# cameraboardschematic.net
KiCad netlist of a schematic drawn in EasyEDA Pro
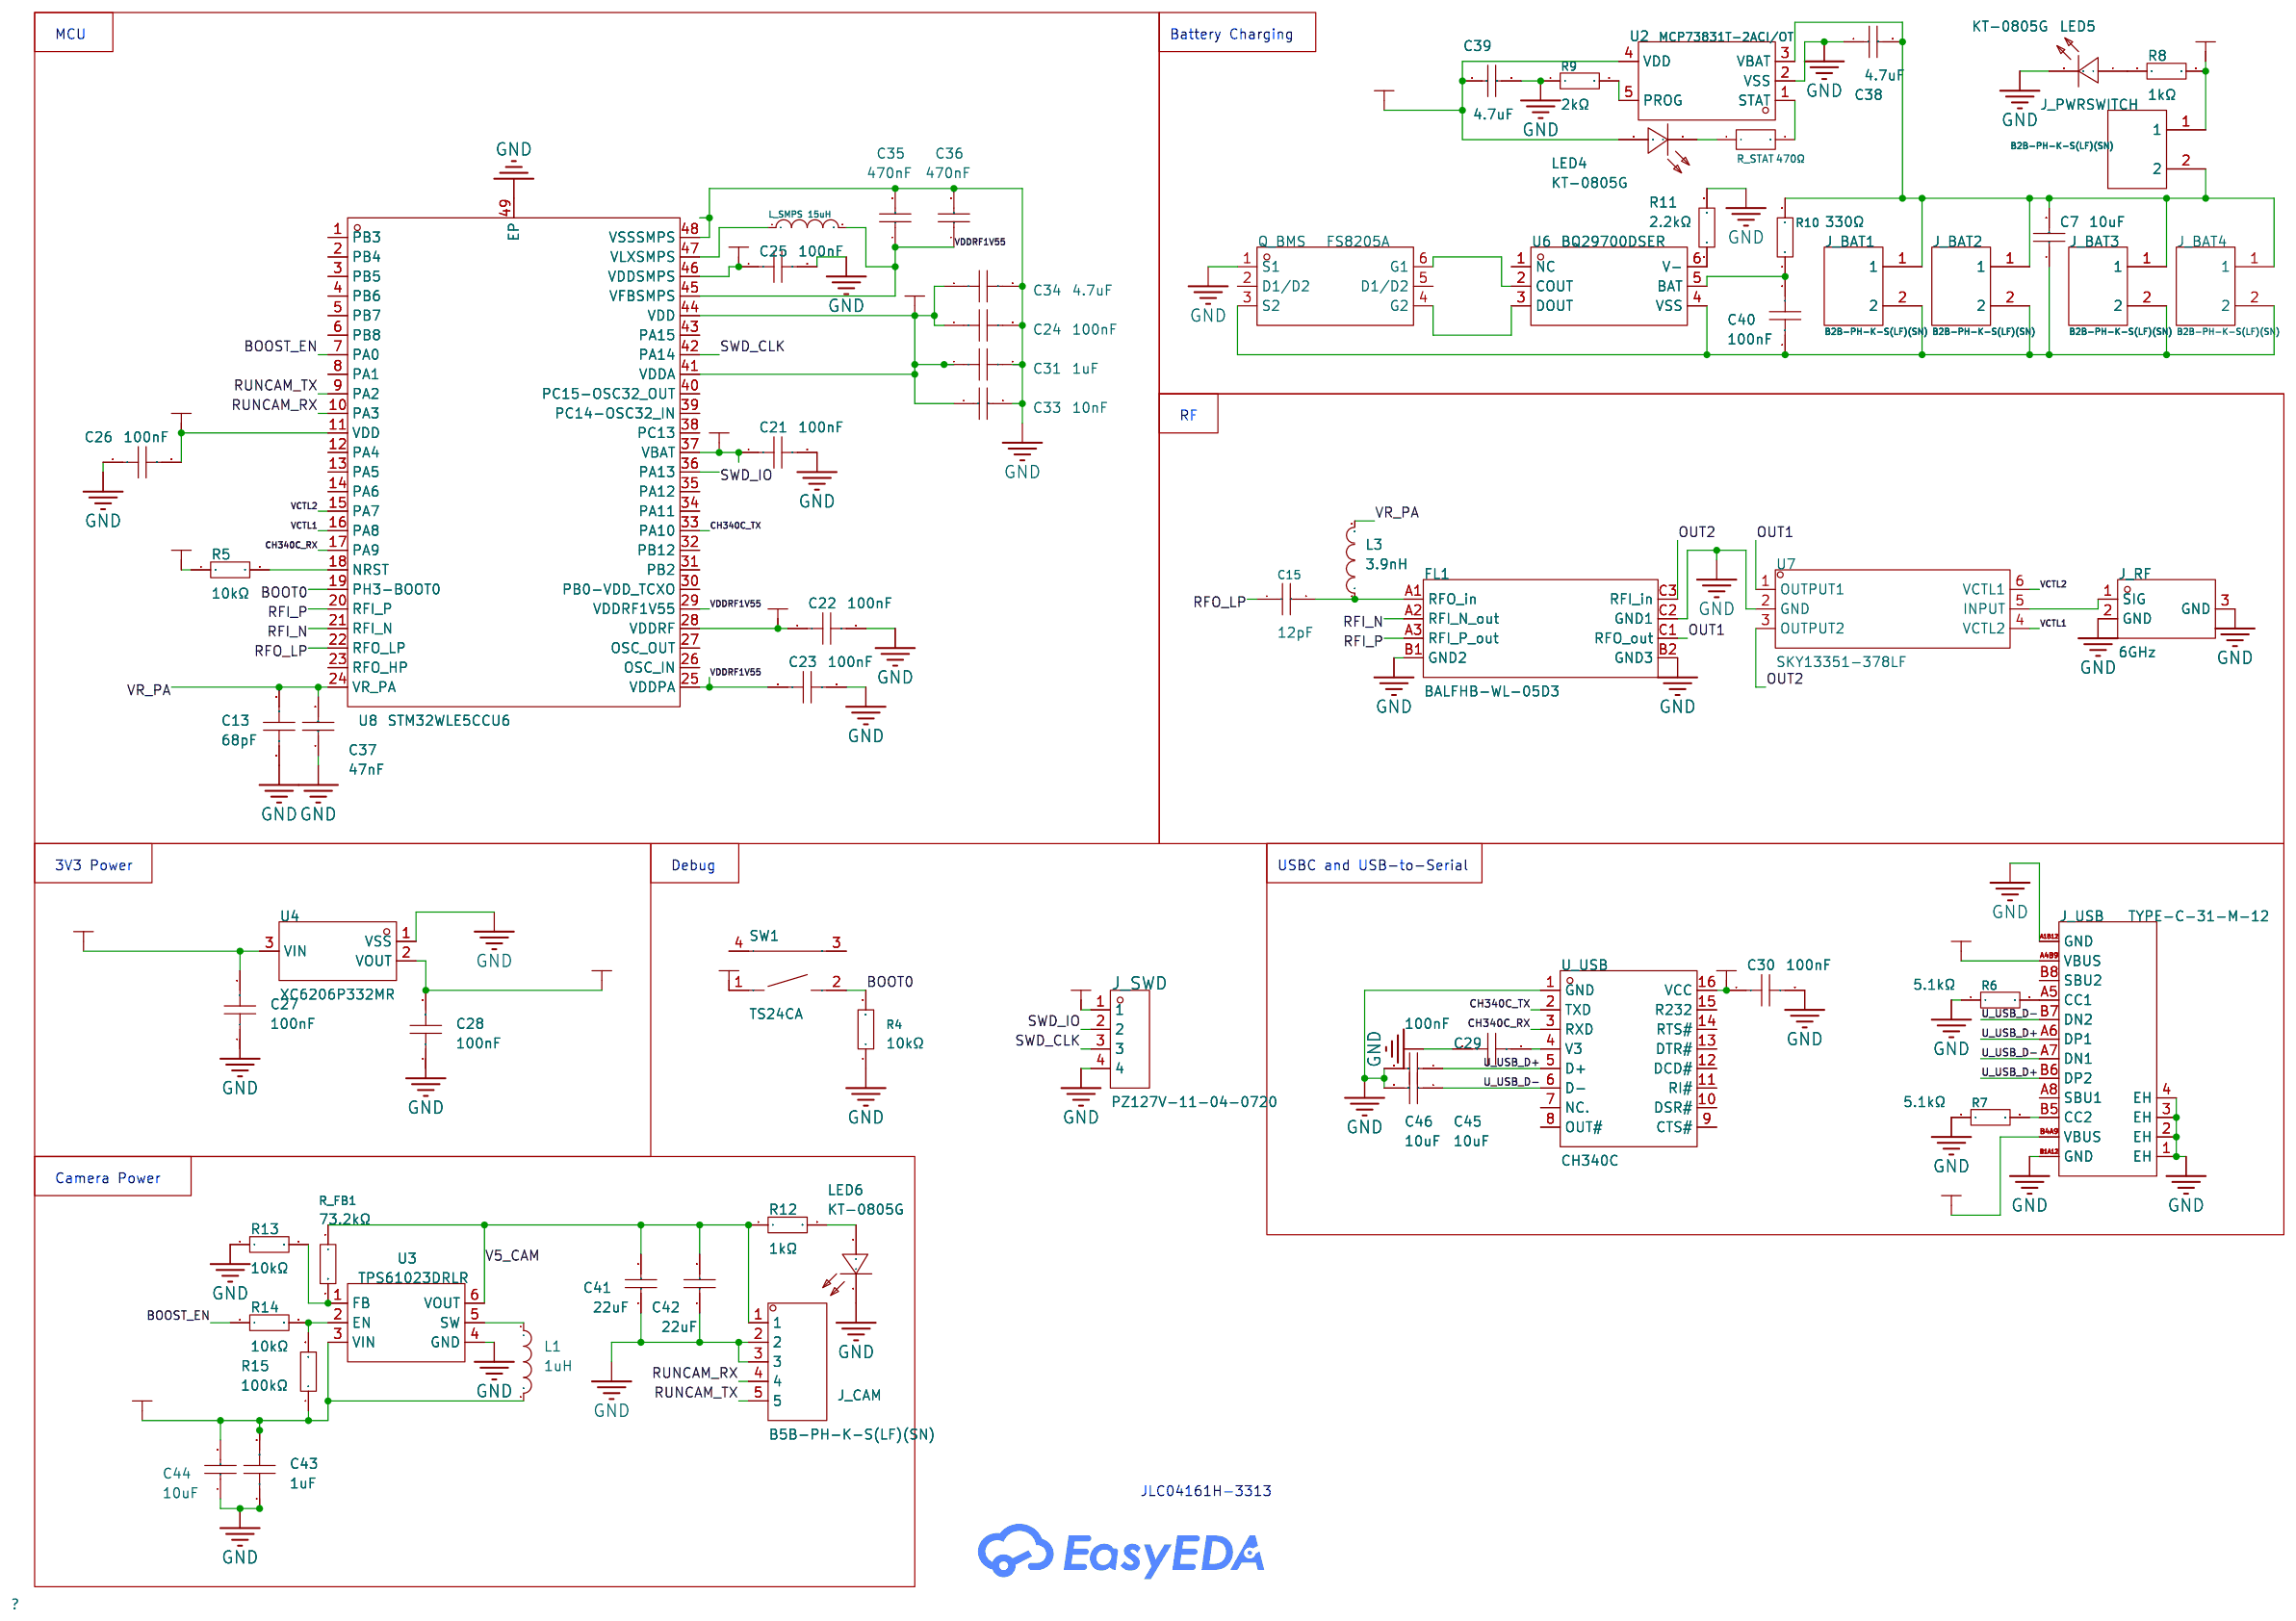
[diagram p0: schematic sheet]

(export (version "E")
  (design (tool "Eeschema 10.0.6"))
  (components
    (comp (ref "C7")
      (value "10uF")
      (footprint "easyedapro:C0402")
      (description "Capacitance:10uF Tolerance:±20% Tolerance:±20% Voltage Rating:6.3V Temperature Coefficient:X5R")
      (fields
        (field (name "Manufacturer Part") "CL05A106MQ5NUNC")
        (field (name "Manufacturer") "SAMSUNG(三星)")
      )
      (libsource (lib "easyedapro") (part "CL05A106MQ5NUNC"))
    )
    (comp (ref "C13")
      (value "68pF")
      (footprint "easyedapro:C0402")
      (description "Capacitance:68pF Tolerance:±5% Tolerance:±5% Voltage Rating:50V Temperature Coefficient:C0G")
      (fields (field (name "Manufacturer Part") "0402CG680J500NT") (field (name "Manufacturer") "FH(风华)"))
      (libsource (lib "easyedapro") (part "0402CG680J500NT"))
    )
    (comp (ref "C15")
      (value "12pF")
      (footprint "easyedapro:C0402")
      (description "Capacitance:12pF Tolerance:±5% Tolerance:±5% Voltage Rating:50V Temperature Coefficient:NP0")
      (fields
        (field (name "Manufacturer Part") "CC0402JRNPO9BN120")
        (field (name "Manufacturer") "YAGEO(国巨)")
      )
      (libsource (lib "easyedapro") (part "CC0402JRNPO9BN120"))
    )
    (comp (ref "C21")
      (value "100nF")
      (footprint "easyedapro:C0402")
      (description "Capacitance:100nF Tolerance:±10% Tolerance:±10% Voltage Rating:16V Temperature Coefficient:X7R")
      (fields
        (field (name "Manufacturer Part") "CL05B104KO5NNNC")
        (field (name "Manufacturer") "SAMSUNG(三星)")
      )
      (libsource (lib "easyedapro") (part "CL05B104KO5NNNC"))
    )
    (comp (ref "C22")
      (value "100nF")
      (footprint "easyedapro:C0402")
      (description "Capacitance:100nF Tolerance:±10% Tolerance:±10% Voltage Rating:16V Temperature Coefficient:X7R")
      (fields
        (field (name "Manufacturer Part") "CL05B104KO5NNNC")
        (field (name "Manufacturer") "SAMSUNG(三星)")
      )
      (libsource (lib "easyedapro") (part "CL05B104KO5NNNC"))
    )
    (comp (ref "C23")
      (value "100nF")
      (footprint "easyedapro:C0402")
      (description "Capacitance:100nF Tolerance:±10% Tolerance:±10% Voltage Rating:16V Temperature Coefficient:X7R")
      (fields
        (field (name "Manufacturer Part") "CL05B104KO5NNNC")
        (field (name "Manufacturer") "SAMSUNG(三星)")
      )
      (libsource (lib "easyedapro") (part "CL05B104KO5NNNC"))
    )
    (comp (ref "C24")
      (value "100nF")
      (footprint "easyedapro:C0402")
      (description "Capacitance:100nF Tolerance:±10% Tolerance:±10% Voltage Rating:16V Temperature Coefficient:X7R")
      (fields
        (field (name "Manufacturer Part") "CL05B104KO5NNNC")
        (field (name "Manufacturer") "SAMSUNG(三星)")
      )
      (libsource (lib "easyedapro") (part "CL05B104KO5NNNC"))
    )
    (comp (ref "C25")
      (value "100nF")
      (footprint "easyedapro:C0402")
      (description "Capacitance:100nF Tolerance:±10% Tolerance:±10% Voltage Rating:16V Temperature Coefficient:X7R")
      (fields
        (field (name "Manufacturer Part") "CL05B104KO5NNNC")
        (field (name "Manufacturer") "SAMSUNG(三星)")
      )
      (libsource (lib "easyedapro") (part "CL05B104KO5NNNC"))
    )
    (comp (ref "C26")
      (value "100nF")
      (footprint "easyedapro:C0402")
      (description "Capacitance:100nF Tolerance:±10% Tolerance:±10% Voltage Rating:16V Temperature Coefficient:X7R")
      (fields
        (field (name "Manufacturer Part") "CL05B104KO5NNNC")
        (field (name "Manufacturer") "SAMSUNG(三星)")
      )
      (libsource (lib "easyedapro") (part "CL05B104KO5NNNC"))
    )
    (comp (ref "C27")
      (value "100nF")
      (footprint "easyedapro:C0402")
      (description "Capacitance:100nF Tolerance:±10% Tolerance:±10% Voltage Rating:16V Temperature Coefficient:X7R")
      (fields
        (field (name "Manufacturer Part") "CL05B104KO5NNNC")
        (field (name "Manufacturer") "SAMSUNG(三星)")
      )
      (libsource (lib "easyedapro") (part "CL05B104KO5NNNC"))
    )
    (comp (ref "C28")
      (value "100nF")
      (footprint "easyedapro:C0402")
      (description "Capacitance:100nF Tolerance:±10% Tolerance:±10% Voltage Rating:16V Temperature Coefficient:X7R")
      (fields
        (field (name "Manufacturer Part") "CL05B104KO5NNNC")
        (field (name "Manufacturer") "SAMSUNG(三星)")
      )
      (libsource (lib "easyedapro") (part "CL05B104KO5NNNC"))
    )
    (comp (ref "C29")
      (value "100nF")
      (footprint "easyedapro:C0402")
      (description "Capacitance:100nF Tolerance:±10% Tolerance:±10% Voltage Rating:16V Temperature Coefficient:X7R")
      (fields
        (field (name "Manufacturer Part") "CL05B104KO5NNNC")
        (field (name "Manufacturer") "SAMSUNG(三星)")
      )
      (libsource (lib "easyedapro") (part "CL05B104KO5NNNC"))
    )
    (comp (ref "C30")
      (value "100nF")
      (footprint "easyedapro:C0402")
      (description "Capacitance:100nF Tolerance:±10% Tolerance:±10% Voltage Rating:16V Temperature Coefficient:X7R")
      (fields
        (field (name "Manufacturer Part") "CL05B104KO5NNNC")
        (field (name "Manufacturer") "SAMSUNG(三星)")
      )
      (libsource (lib "easyedapro") (part "CL05B104KO5NNNC"))
    )
    (comp (ref "C31")
      (value "1uF")
      (footprint "easyedapro:C0402")
      (description "Capacitance:1uF Tolerance:±10% Tolerance:±10% Voltage Rating:25V Temperature Coefficient:X5R")
      (fields
        (field (name "Manufacturer Part") "CL05A105KA5NQNC")
        (field (name "Manufacturer") "SAMSUNG(三星)")
      )
      (libsource (lib "easyedapro") (part "CL05A105KA5NQNC"))
    )
    (comp (ref "C33")
      (value "10nF")
      (footprint "easyedapro:C0402")
      (description "Capacitance:10nF Tolerance:±10% Tolerance:±10% Voltage Rating:50V Temperature Coefficient:X7R")
      (fields
        (field (name "Manufacturer Part") "CL05B103KB5NNNC")
        (field (name "Manufacturer") "SAMSUNG(三星)")
      )
      (libsource (lib "easyedapro") (part "CL05B103KB5NNNC"))
    )
    (comp (ref "C34")
      (value "4.7uF")
      (footprint "easyedapro:C0402")
      (description "Capacitance:4.7uF Tolerance:±20% Tolerance:±20% Voltage Rating:10V Temperature Coefficient:X5R")
      (fields
        (field (name "Manufacturer Part") "CL05A475MP5NRNC")
        (field (name "Manufacturer") "SAMSUNG(三星)")
      )
      (libsource (lib "easyedapro") (part "CL05A475MP5NRNC"))
    )
    (comp (ref "C35")
      (value "470nF")
      (footprint "easyedapro:C0603")
      (description "Capacitance:470nF Tolerance:±10% Tolerance:±10% Voltage Rating:25V Temperature Coefficient:X7R")
      (fields
        (field (name "Manufacturer Part") "CL10B474KA8NNNC")
        (field (name "Manufacturer") "SAMSUNG(三星)")
      )
      (libsource (lib "easyedapro") (part "CL10B474KA8NNNC"))
    )
    (comp (ref "C36")
      (value "470nF")
      (footprint "easyedapro:C0603")
      (description "Capacitance:470nF Tolerance:±10% Tolerance:±10% Voltage Rating:25V Temperature Coefficient:X7R")
      (fields
        (field (name "Manufacturer Part") "CL10B474KA8NNNC")
        (field (name "Manufacturer") "SAMSUNG(三星)")
      )
      (libsource (lib "easyedapro") (part "CL10B474KA8NNNC"))
    )
    (comp (ref "C37")
      (value "47nF")
      (footprint "easyedapro:C0402")
      (description "Capacitance:47nF Tolerance:±10% Tolerance:±10% Voltage Rating:50V Temperature Coefficient:X7R")
      (fields (field (name "Manufacturer Part") "0402B473K500NT") (field (name "Manufacturer") "FH(风华)"))
      (libsource (lib "easyedapro") (part "0402B473K500NT"))
    )
    (comp (ref "C38")
      (value "4.7uF")
      (footprint "easyedapro:C1206")
      (description "Capacitance:4.7uF Tolerance:±10% Tolerance:±10% Voltage Rating:25V Temperature Coefficient:X7R")
      (fields
        (field (name "Manufacturer Part") "CL31B475KAHNNNE")
        (field (name "Manufacturer") "SAMSUNG(三星)")
      )
      (libsource (lib "easyedapro") (part "CL31B475KAHNNNE"))
    )
    (comp (ref "C39")
      (value "4.7uF")
      (footprint "easyedapro:C1206")
      (description "Capacitance:4.7uF Tolerance:±10% Tolerance:±10% Voltage Rating:25V Temperature Coefficient:X7R")
      (fields
        (field (name "Manufacturer Part") "CL31B475KAHNNNE")
        (field (name "Manufacturer") "SAMSUNG(三星)")
      )
      (libsource (lib "easyedapro") (part "CL31B475KAHNNNE"))
    )
    (comp (ref "C40")
      (value "100nF")
      (footprint "easyedapro:C0402")
      (description "Capacitance:100nF Tolerance:±10% Tolerance:±10% Voltage Rating:16V Temperature Coefficient:X7R")
      (fields
        (field (name "Manufacturer Part") "CL05B104KO5NNNC")
        (field (name "Manufacturer") "SAMSUNG(三星)")
      )
      (libsource (lib "easyedapro") (part "CL05B104KO5NNNC"))
    )
    (comp (ref "C41")
      (value "22uF")
      (footprint "easyedapro:C1206")
      (description "Capacitance:22uF Tolerance:±10% Tolerance:±10% Voltage Rating:25V Temperature Coefficient:X5R")
      (fields
        (field (name "Manufacturer Part") "CL31A226KAHNNNE")
        (field (name "Manufacturer") "SAMSUNG(三星)")
      )
      (libsource (lib "easyedapro") (part "CL31A226KAHNNNE"))
    )
    (comp (ref "C42")
      (value "22uF")
      (footprint "easyedapro:C1206")
      (description "Capacitance:22uF Tolerance:±10% Tolerance:±10% Voltage Rating:25V Temperature Coefficient:X5R")
      (fields
        (field (name "Manufacturer Part") "CL31A226KAHNNNE")
        (field (name "Manufacturer") "SAMSUNG(三星)")
      )
      (libsource (lib "easyedapro") (part "CL31A226KAHNNNE"))
    )
    (comp (ref "C43")
      (value "1uF")
      (footprint "easyedapro:C0402")
      (description "Capacitance:1uF Tolerance:±10% Tolerance:±10% Voltage Rating:25V Temperature Coefficient:X5R")
      (fields
        (field (name "Manufacturer Part") "CL05A105KA5NQNC")
        (field (name "Manufacturer") "SAMSUNG(三星)")
      )
      (libsource (lib "easyedapro") (part "CL05A105KA5NQNC"))
    )
    (comp (ref "C44")
      (value "10uF")
      (footprint "easyedapro:C0402")
      (description "Capacitance:10uF Tolerance:±20% Tolerance:±20% Voltage Rating:6.3V Temperature Coefficient:X5R")
      (fields
        (field (name "Manufacturer Part") "CL05A106MQ5NUNC")
        (field (name "Manufacturer") "SAMSUNG(三星)")
      )
      (libsource (lib "easyedapro") (part "CL05A106MQ5NUNC"))
    )
    (comp (ref "C45")
      (value "10uF")
      (footprint "easyedapro:C0402")
      (description "Capacitance:10uF Tolerance:±20% Tolerance:±20% Voltage Rating:6.3V Temperature Coefficient:X5R")
      (fields
        (field (name "Manufacturer Part") "CL05A106MQ5NUNC")
        (field (name "Manufacturer") "SAMSUNG(三星)")
      )
      (libsource (lib "easyedapro") (part "CL05A106MQ5NUNC"))
    )
    (comp (ref "C46")
      (value "10uF")
      (footprint "easyedapro:C0402")
      (description "Capacitance:10uF Tolerance:±20% Tolerance:±20% Voltage Rating:6.3V Temperature Coefficient:X5R")
      (fields
        (field (name "Manufacturer Part") "CL05A106MQ5NUNC")
        (field (name "Manufacturer") "SAMSUNG(三星)")
      )
      (libsource (lib "easyedapro") (part "CL05A106MQ5NUNC"))
    )
    (comp (ref "FL1")
      (value "BALFHB-WL-05D3")
      (footprint "easyedapro:CSPG-8_L2.1-W1.8_BALFHB-WL-03D3")
      (fields (field (name "Manufacturer") "ST(意法半导体)"))
      (libsource (lib "easyedapro") (part "BALFHB-WL-05D3"))
    )
    (comp (ref "J_BAT1")
      (value "B2B-PH-K-S(LF)(SN)")
      (footprint "easyedapro:CONN-TH_B2B-PH-K-S")
      (fields (field (name "Manufacturer") "JST"))
      (libsource (lib "easyedapro") (part "B2B-PH-K-S(LF)(SN)"))
    )
    (comp (ref "J_BAT2")
      (value "B2B-PH-K-S(LF)(SN)")
      (footprint "easyedapro:CONN-TH_B2B-PH-K-S")
      (fields (field (name "Manufacturer") "JST"))
      (libsource (lib "easyedapro") (part "B2B-PH-K-S(LF)(SN)"))
    )
    (comp (ref "J_BAT3")
      (value "B2B-PH-K-S(LF)(SN)")
      (footprint "easyedapro:CONN-TH_B2B-PH-K-S")
      (fields (field (name "Manufacturer") "JST"))
      (libsource (lib "easyedapro") (part "B2B-PH-K-S(LF)(SN)"))
    )
    (comp (ref "J_BAT4")
      (value "B2B-PH-K-S(LF)(SN)")
      (footprint "easyedapro:CONN-TH_B2B-PH-K-S")
      (fields (field (name "Manufacturer") "JST"))
      (libsource (lib "easyedapro") (part "B2B-PH-K-S(LF)(SN)"))
    )
    (comp (ref "J_CAM")
      (value "B5B-PH-K-S(LF)(SN)")
      (footprint "easyedapro:CONN-TH_B5B-PH-K-S-LF-SN")
      (fields (field (name "Manufacturer") "JST"))
      (libsource (lib "easyedapro") (part "B5B-PH-K-S-(LF)(SN)"))
    )
    (comp (ref "J_PWRSWITCH")
      (value "B2B-PH-K-S(LF)(SN)")
      (footprint "easyedapro:CONN-TH_B2B-PH-K-S")
      (fields (field (name "Manufacturer") "JST"))
      (libsource (lib "easyedapro") (part "B2B-PH-K-S(LF)(SN)"))
    )
    (comp (ref "J_RF")
      (value "6GHz")
      (footprint "easyedapro:IPEX-SMD_BWIPX-1-001E")
      (fields
        (field (name "Manufacturer Part") "BWIPX-1-001E")
        (field (name "Manufacturer") "BAT WIRELESS(蝙蝠无线)")
      )
      (libsource (lib "easyedapro") (part "BWIPX-1-001E"))
    )
    (comp (ref "J_SWD")
      (value "PZ127V-11-04-0720")
      (footprint "easyedapro:HDR-TH_4P-P1.27-V-M")
      (fields (field (name "Manufacturer") "XFCN(兴飞)"))
      (libsource (lib "easyedapro") (part "PZ127V-11-04-0720"))
    )
    (comp (ref "J_USB")
      (value "TYPE-C-31-M-12")
      (footprint "easyedapro:USB-C_SMD-TYPE-C-31-M-12_1")
      (fields (field (name "Manufacturer") "韩国韩荣"))
      (libsource (lib "easyedapro") (part "TYPE-C-31-M-12"))
    )
    (comp (ref "L1")
      (value "1uH")
      (footprint "easyedapro:L0603")
      (fields (field (name "Manufacturer Part") "YL160808-1R0K") (field (name "Manufacturer") "YJYCOIN(益嘉源)"))
      (libsource (lib "easyedapro") (part "YL160808-1R0K"))
    )
    (comp (ref "L3")
      (value "3.9nH")
      (footprint "easyedapro:IND-SMD_L1.0-W0.5-2")
      (fields (field (name "Manufacturer Part") "LQW15AN3N9B00D") (field (name "Manufacturer") "muRata(村田)"))
      (libsource (lib "easyedapro") (part "LQW15AN3N9B00D"))
    )
    (comp (ref "LED4")
      (value "KT-0805G")
      (footprint "easyedapro:LED0805-R-RD")
      (fields (field (name "Manufacturer") "KENTO"))
      (libsource (lib "easyedapro") (part "0805G (Green)"))
    )
    (comp (ref "LED5")
      (value "KT-0805G")
      (footprint "easyedapro:LED0805-R-RD")
      (fields (field (name "Manufacturer") "KENTO"))
      (libsource (lib "easyedapro") (part "0805G (Green)"))
    )
    (comp (ref "LED6")
      (value "KT-0805G")
      (footprint "easyedapro:LED0805-R-RD")
      (fields (field (name "Manufacturer") "KENTO"))
      (libsource (lib "easyedapro") (part "0805G (Green)"))
    )
    (comp (ref "L_SMPS")
      (value "15uH")
      (footprint "easyedapro:IND-SMD_L2.5-W2.0")
      (fields (field (name "Manufacturer Part") "XRNR252010-15uH/M") (field (name "Manufacturer") "XR(祥如)"))
      (libsource (lib "easyedapro") (part "XRNR252010-15UH/M"))
    )
    (comp (ref "Q_BMS")
      (value "FS8205A")
      (footprint "easyedapro:SOT-23-6_L2.9-W1.6-P0.95-LS2.8-BR")
      (fields (field (name "Manufacturer") "TECH PUBLIC(台舟)"))
      (libsource (lib "easyedapro") (part "FS8205A_C2830320"))
    )
    (comp (ref "R4")
      (value "10kΩ")
      (footprint "easyedapro:R0402")
      (fields (field (name "Manufacturer Part") "RC0402JR-0710KL") (field (name "Manufacturer") "YAGEO(国巨)"))
      (libsource (lib "easyedapro") (part "RC0402JR-0710KL"))
    )
    (comp (ref "R5")
      (value "10kΩ")
      (footprint "easyedapro:R0402")
      (fields
        (field (name "Manufacturer Part") "0402WGF1002TCE")
        (field (name "Manufacturer") "UNI-ROYAL(厚声)")
      )
      (libsource (lib "easyedapro") (part "0402WGF1002TCE"))
    )
    (comp (ref "R6")
      (value "5.1kΩ")
      (footprint "easyedapro:R0402")
      (fields
        (field (name "Manufacturer Part") "0402WGF5101TCE")
        (field (name "Manufacturer") "UNI-ROYAL(厚声)")
      )
      (libsource (lib "easyedapro") (part "0402WGF5101TCE"))
    )
    (comp (ref "R7")
      (value "5.1kΩ")
      (footprint "easyedapro:R0402")
      (fields
        (field (name "Manufacturer Part") "0402WGF5101TCE")
        (field (name "Manufacturer") "UNI-ROYAL(厚声)")
      )
      (libsource (lib "easyedapro") (part "0402WGF5101TCE"))
    )
    (comp (ref "R8")
      (value "1kΩ")
      (footprint "easyedapro:R0402")
      (fields
        (field (name "Manufacturer Part") "0402WGF1001TCE")
        (field (name "Manufacturer") "UNI-ROYAL(厚声)")
      )
      (libsource (lib "easyedapro") (part "0402WGF1001TCE"))
    )
    (comp (ref "R9")
      (value "2kΩ")
      (footprint "easyedapro:R0402")
      (fields
        (field (name "Manufacturer Part") "0402WGF2001TCE")
        (field (name "Manufacturer") "UNI-ROYAL(厚声)")
      )
      (libsource (lib "easyedapro") (part "0402WGF2001TCE"))
    )
    (comp (ref "R10")
      (value "330Ω")
      (footprint "easyedapro:R0805")
      (fields
        (field (name "Manufacturer Part") "0805W8F3300T5E")
        (field (name "Manufacturer") "UNI-ROYAL(厚声)")
      )
      (libsource (lib "easyedapro") (part "0805W8F3300T5E"))
    )
    (comp (ref "R11")
      (value "2.2kΩ")
      (footprint "easyedapro:R0805")
      (fields
        (field (name "Manufacturer Part") "0805W8F2201T5E")
        (field (name "Manufacturer") "UNI-ROYAL(厚声)")
      )
      (libsource (lib "easyedapro") (part "0805W8F2201T5E"))
    )
    (comp (ref "R12")
      (value "1kΩ")
      (footprint "easyedapro:R0402")
      (fields
        (field (name "Manufacturer Part") "0402WGF1001TCE")
        (field (name "Manufacturer") "UNI-ROYAL(厚声)")
      )
      (libsource (lib "easyedapro") (part "0402WGF1001TCE"))
    )
    (comp (ref "R13")
      (value "10kΩ")
      (footprint "easyedapro:R0402")
      (fields
        (field (name "Manufacturer Part") "0402WGF1002TCE")
        (field (name "Manufacturer") "UNI-ROYAL(厚声)")
      )
      (libsource (lib "easyedapro") (part "0402WGF1002TCE"))
    )
    (comp (ref "R14")
      (value "10kΩ")
      (footprint "easyedapro:R0402")
      (fields
        (field (name "Manufacturer Part") "0402WGF1002TCE")
        (field (name "Manufacturer") "UNI-ROYAL(厚声)")
      )
      (libsource (lib "easyedapro") (part "0402WGF1002TCE"))
    )
    (comp (ref "R15")
      (value "100kΩ")
      (footprint "easyedapro:R1206")
      (fields
        (field (name "Manufacturer Part") "1206W4F1003T5E")
        (field (name "Manufacturer") "UNI-ROYAL(厚声)")
      )
      (libsource (lib "easyedapro") (part "1206W4F1003T5E"))
    )
    (comp (ref "R_FB1")
      (value "73.2kΩ")
      (footprint "easyedapro:R0402")
      (fields
        (field (name "Manufacturer Part") "0402WGF7322TCE")
        (field (name "Manufacturer") "UNI-ROYAL(厚声)")
      )
      (libsource (lib "easyedapro") (part "0402WGF7322TCE"))
    )
    (comp (ref "R_STAT")
      (value "470Ω")
      (footprint "easyedapro:R0402")
      (fields (field (name "Manufacturer Part") "FRC0402F4700TS") (field (name "Manufacturer") "FOJAN(富捷)"))
      (libsource (lib "easyedapro") (part "FRC0402F4700TS"))
    )
    (comp (ref "SW1")
      (value "TS24CA")
      (footprint "easyedapro:SW-SMD_2P-TS24CA")
      (fields (field (name "Manufacturer") "SHOU HAN(首韩)"))
      (libsource (lib "easyedapro") (part "TS24CA"))
    )
    (comp (ref "U2")
      (value "MCP73831T-2ACI/OT")
      (footprint "easyedapro:SOT-23-5_L3.0-W1.7-P0.95-LS2.8-BL")
      (fields (field (name "Manufacturer") "MICROCHIP(美国微芯)"))
      (libsource (lib "easyedapro") (part "MCP73831T-2ACI/OT"))
    )
    (comp (ref "U3")
      (value "TPS61023DRLR")
      (footprint "easyedapro:SOT-563_L1.6-W1.2-P0.50-LS1.6-BR")
      (fields (field (name "Manufacturer") "TI(德州仪器)"))
      (libsource (lib "easyedapro") (part "TPS61023DRLR"))
    )
    (comp (ref "U4")
      (value "XC6206P332MR")
      (footprint "easyedapro:SOT-23-3_L3.0-W1.7-P0.95-LS2.9-BR")
      (fields (field (name "Manufacturer") "UMW(友台半导体)"))
      (libsource (lib "easyedapro") (part "XC6206P332MR_C347376"))
    )
    (comp (ref "U6")
      (value "BQ29700DSER")
      (footprint "easyedapro:WSON-6_L1.5-W1.5-P0.50-TL")
      (fields (field (name "Manufacturer") "TI(德州仪器)"))
      (libsource (lib "easyedapro") (part "BQ29700DSER"))
    )
    (comp (ref "U7")
      (value "SKY13351-378LF")
      (footprint "easyedapro:DFN-6_L1.0-W1.0-P0.35-BL-EP0.15")
      (fields (field (name "Manufacturer") "SKYWORKS"))
      (libsource (lib "easyedapro") (part "SKY13351-378LF"))
    )
    (comp (ref "U8")
      (value "STM32WLE5CCU6")
      (footprint "easyedapro:UFQFPN-48_L7.0-W7.0-P0.50-BL-EP5.6")
      (fields (field (name "Manufacturer") "ST(意法半导体)"))
      (libsource (lib "easyedapro") (part "STM32WLE5CCU6"))
    )
    (comp (ref "U_USB")
      (value "CH340C")
      (footprint "easyedapro:SOP-16_L10.0-W3.9-P1.27-LS6.0-BL")
      (fields (field (name "Manufacturer") "WCH(南京沁恒)"))
      (libsource (lib "easyedapro") (part "CH340C"))
    )
  )
  (nets
    (net (code "1") (name "/BOOST_EN") (class "Default")
      (node (ref "R14") (pin "1") (pinfunction "1_1") (pintype "input"))
      (node (ref "U8") (pin "7") (pinfunction "PA0_7") (pintype "unspecified"))
    )
    (net (code "2") (name "/BOOT0") (class "Default")
      (node (ref "R4") (pin "2") (pinfunction "2_2") (pintype "input"))
      (node (ref "SW1") (pin "2") (pinfunction "2_2") (pintype "unspecified"))
      (node (ref "U8") (pin "19") (pinfunction "PH3-BOOT0_19") (pintype "unspecified"))
    )
    (net (code "3") (name "/CH340C_RX") (class "Default")
      (node (ref "U8") (pin "17") (pinfunction "PA9_17") (pintype "unspecified"))
      (node (ref "U_USB") (pin "3") (pinfunction "RXD_3") (pintype "unspecified"))
    )
    (net (code "4") (name "/CH340C_TX") (class "Default")
      (node (ref "U8") (pin "33") (pinfunction "PA10_33") (pintype "unspecified"))
      (node (ref "U_USB") (pin "2") (pinfunction "TXD_2") (pintype "unspecified"))
    )
    (net (code "5") (name "/OUT1") (class "Default")
      (node (ref "FL1") (pin "C1") (pinfunction "RFO_out_C1") (pintype "unspecified"))
      (node (ref "U7") (pin "1") (pinfunction "OUTPUT1_1") (pintype "unspecified"))
    )
    (net (code "6") (name "/OUT2") (class "Default")
      (node (ref "FL1") (pin "C3") (pinfunction "RFI_in_C3") (pintype "unspecified"))
      (node (ref "U7") (pin "3") (pinfunction "OUTPUT2_3") (pintype "unspecified"))
    )
    (net (code "7") (name "/RFI_N") (class "Default")
      (node (ref "FL1") (pin "A2") (pinfunction "RFI_N_out_A2") (pintype "unspecified"))
      (node (ref "U8") (pin "21") (pinfunction "RFI_N_21") (pintype "unspecified"))
    )
    (net (code "8") (name "/RFI_P") (class "Default")
      (node (ref "FL1") (pin "A3") (pinfunction "RFI_P_out_A3") (pintype "unspecified"))
      (node (ref "U8") (pin "20") (pinfunction "RFI_P_20") (pintype "unspecified"))
    )
    (net (code "9") (name "/RFO_LP") (class "Default")
      (node (ref "C15") (pin "1") (pinfunction "1_1") (pintype "input"))
      (node (ref "U8") (pin "22") (pinfunction "RFO_LP_22") (pintype "unspecified"))
    )
    (net (code "10") (name "/RUNCAM_RX") (class "Default")
      (node (ref "J_CAM") (pin "4") (pinfunction "4_4") (pintype "unspecified"))
      (node (ref "U8") (pin "10") (pinfunction "PA3_10") (pintype "unspecified"))
    )
    (net (code "11") (name "/RUNCAM_TX") (class "Default")
      (node (ref "J_CAM") (pin "5") (pinfunction "5_5") (pintype "unspecified"))
      (node (ref "U8") (pin "9") (pinfunction "PA2_9") (pintype "unspecified"))
    )
    (net (code "12") (name "/SWD_CLK") (class "Default")
      (node (ref "J_SWD") (pin "3") (pinfunction "3_3") (pintype "input"))
      (node (ref "U8") (pin "42") (pinfunction "PA14_42") (pintype "unspecified"))
    )
    (net (code "13") (name "/SWD_IO") (class "Default")
      (node (ref "J_SWD") (pin "2") (pinfunction "2_2") (pintype "input"))
      (node (ref "U8") (pin "36") (pinfunction "PA13_36") (pintype "unspecified"))
    )
    (net (code "14") (name "/U_USB_D+") (class "Default")
      (node (ref "C45") (pin "1") (pinfunction "1_1") (pintype "input"))
      (node (ref "J_USB") (pin "A6") (pinfunction "DP1_A6") (pintype "unspecified"))
      (node (ref "J_USB") (pin "B6") (pinfunction "DP2_B6") (pintype "unspecified"))
      (node (ref "U_USB") (pin "5") (pinfunction "D+_5") (pintype "unspecified"))
    )
    (net (code "15") (name "/U_USB_D-") (class "Default")
      (node (ref "C46") (pin "1") (pinfunction "1_1") (pintype "input"))
      (node (ref "J_USB") (pin "A7") (pinfunction "DN1_A7") (pintype "unspecified"))
      (node (ref "J_USB") (pin "B7") (pinfunction "DN2_B7") (pintype "unspecified"))
      (node (ref "U_USB") (pin "6") (pinfunction "D-_6") (pintype "unspecified"))
    )
    (net (code "16") (name "/V5_CAM") (class "Default")
      (node (ref "C41") (pin "2") (pinfunction "2_2") (pintype "input"))
      (node (ref "C42") (pin "2") (pinfunction "2_2") (pintype "input"))
      (node (ref "J_CAM") (pin "1") (pinfunction "1_1") (pintype "unspecified"))
      (node (ref "R12") (pin "1") (pinfunction "1_1") (pintype "input"))
      (node (ref "R_FB1") (pin "1") (pinfunction "1_1") (pintype "input"))
      (node (ref "U3") (pin "6") (pinfunction "VOUT_6") (pintype "unspecified"))
    )
    (net (code "17") (name "/VCTL1") (class "Default")
      (node (ref "U7") (pin "4") (pinfunction "VCTL2_4") (pintype "unspecified"))
      (node (ref "U8") (pin "16") (pinfunction "PA8_16") (pintype "unspecified"))
    )
    (net (code "18") (name "/VCTL2") (class "Default")
      (node (ref "U7") (pin "6") (pinfunction "VCTL1_6") (pintype "unspecified"))
      (node (ref "U8") (pin "15") (pinfunction "PA7_15") (pintype "unspecified"))
    )
    (net (code "19") (name "/VDDRF1V55") (class "Default")
      (node (ref "C23") (pin "1") (pinfunction "1_1") (pintype "unspecified"))
      (node (ref "C35") (pin "1") (pinfunction "1_1") (pintype "input"))
      (node (ref "C36") (pin "1") (pinfunction "1_1") (pintype "input"))
      (node (ref "L_SMPS") (pin "2") (pinfunction "2_2") (pintype "unspecified"))
      (node (ref "U8") (pin "25") (pinfunction "VDDPA_25") (pintype "unspecified"))
      (node (ref "U8") (pin "29") (pinfunction "VDDRF1V55_29") (pintype "unspecified"))
      (node (ref "U8") (pin "45") (pinfunction "VFBSMPS_45") (pintype "unspecified"))
    )
    (net (code "20") (name "/VR_PA") (class "Default")
      (node (ref "C13") (pin "2") (pinfunction "2_2") (pintype "unspecified"))
      (node (ref "C37") (pin "2") (pinfunction "2_2") (pintype "input"))
      (node (ref "L3") (pin "2") (pinfunction "2_2") (pintype "unspecified"))
      (node (ref "U8") (pin "24") (pinfunction "VR_PA_24") (pintype "unspecified"))
    )
    (net (code "21") (name "3V3") (class "Default")
      (node (ref "C21") (pin "1") (pinfunction "1_1") (pintype "unspecified"))
      (node (ref "C22") (pin "1") (pinfunction "1_1") (pintype "unspecified"))
      (node (ref "C24") (pin "1") (pinfunction "1_1") (pintype "unspecified"))
      (node (ref "C25") (pin "1") (pinfunction "1_1") (pintype "unspecified"))
      (node (ref "C26") (pin "2") (pinfunction "2_2") (pintype "unspecified"))
      (node (ref "C28") (pin "2") (pinfunction "2_2") (pintype "unspecified"))
      (node (ref "C30") (pin "1") (pinfunction "1_1") (pintype "unspecified"))
      (node (ref "C31") (pin "1") (pinfunction "1_1") (pintype "unspecified"))
      (node (ref "C33") (pin "1") (pinfunction "1_1") (pintype "input"))
      (node (ref "C34") (pin "1") (pinfunction "1_1") (pintype "unspecified"))
      (node (ref "J_SWD") (pin "1") (pinfunction "1_1") (pintype "input"))
      (node (ref "R5") (pin "1") (pinfunction "1_1") (pintype "input"))
      (node (ref "SW1") (pin "1") (pinfunction "1_1") (pintype "unspecified"))
      (node (ref "U4") (pin "2") (pinfunction "VOUT_2") (pintype "unspecified"))
      (node (ref "U8") (pin "11") (pinfunction "VDD_11") (pintype "unspecified"))
      (node (ref "U8") (pin "28") (pinfunction "VDDRF_28") (pintype "unspecified"))
      (node (ref "U8") (pin "37") (pinfunction "VBAT_37") (pintype "unspecified"))
      (node (ref "U8") (pin "41") (pinfunction "VDDA_41") (pintype "unspecified"))
      (node (ref "U8") (pin "44") (pinfunction "VDD_44") (pintype "unspecified"))
      (node (ref "U8") (pin "46") (pinfunction "VDDSMPS_46") (pintype "unspecified"))
      (node (ref "U_USB") (pin "16") (pinfunction "VCC_16") (pintype "unspecified"))
    )
    (net (code "22") (name "GND") (class "Default")
      (node (ref "C13") (pin "1") (pinfunction "1_1") (pintype "unspecified"))
      (node (ref "C21") (pin "2") (pinfunction "2_2") (pintype "unspecified"))
      (node (ref "C22") (pin "2") (pinfunction "2_2") (pintype "unspecified"))
      (node (ref "C23") (pin "2") (pinfunction "2_2") (pintype "unspecified"))
      (node (ref "C24") (pin "2") (pinfunction "2_2") (pintype "unspecified"))
      (node (ref "C25") (pin "2") (pinfunction "2_2") (pintype "unspecified"))
      (node (ref "C26") (pin "1") (pinfunction "1_1") (pintype "unspecified"))
      (node (ref "C27") (pin "1") (pinfunction "1_1") (pintype "unspecified"))
      (node (ref "C28") (pin "1") (pinfunction "1_1") (pintype "unspecified"))
      (node (ref "C29") (pin "1") (pinfunction "1_1") (pintype "unspecified"))
      (node (ref "C30") (pin "2") (pinfunction "2_2") (pintype "unspecified"))
      (node (ref "C31") (pin "2") (pinfunction "2_2") (pintype "unspecified"))
      (node (ref "C33") (pin "2") (pinfunction "2_2") (pintype "input"))
      (node (ref "C34") (pin "2") (pinfunction "2_2") (pintype "unspecified"))
      (node (ref "C35") (pin "2") (pinfunction "2_2") (pintype "input"))
      (node (ref "C36") (pin "2") (pinfunction "2_2") (pintype "input"))
      (node (ref "C37") (pin "1") (pinfunction "1_1") (pintype "input"))
      (node (ref "C38") (pin "1") (pinfunction "1_1") (pintype "input"))
      (node (ref "C39") (pin "2") (pinfunction "2_2") (pintype "input"))
      (node (ref "C41") (pin "1") (pinfunction "1_1") (pintype "input"))
      (node (ref "C42") (pin "1") (pinfunction "1_1") (pintype "input"))
      (node (ref "C43") (pin "1") (pinfunction "1_1") (pintype "unspecified"))
      (node (ref "C44") (pin "1") (pinfunction "1_1") (pintype "input"))
      (node (ref "C45") (pin "2") (pinfunction "2_2") (pintype "input"))
      (node (ref "C46") (pin "2") (pinfunction "2_2") (pintype "input"))
      (node (ref "FL1") (pin "B1") (pinfunction "GND2_B1") (pintype "unspecified"))
      (node (ref "FL1") (pin "B2") (pinfunction "GND3_B2") (pintype "unspecified"))
      (node (ref "FL1") (pin "C2") (pinfunction "GND1_C2") (pintype "unspecified"))
      (node (ref "J_CAM") (pin "2") (pinfunction "2_2") (pintype "unspecified"))
      (node (ref "J_CAM") (pin "3") (pinfunction "3_3") (pintype "unspecified"))
      (node (ref "J_RF") (pin "2") (pinfunction "GND_2") (pintype "unspecified"))
      (node (ref "J_RF") (pin "3") (pinfunction "GND_3") (pintype "unspecified"))
      (node (ref "J_SWD") (pin "4") (pinfunction "4_4") (pintype "input"))
      (node (ref "J_USB") (pin "1") (pinfunction "EH_1") (pintype "unspecified"))
      (node (ref "J_USB") (pin "2") (pinfunction "EH_2") (pintype "unspecified"))
      (node (ref "J_USB") (pin "3") (pinfunction "EH_3") (pintype "unspecified"))
      (node (ref "J_USB") (pin "4") (pinfunction "EH_4") (pintype "unspecified"))
      (node (ref "J_USB") (pin "A1B12") (pinfunction "GND_A1B12") (pintype "unspecified"))
      (node (ref "J_USB") (pin "B1A12") (pinfunction "GND_B1A12") (pintype "unspecified"))
      (node (ref "LED5") (pin "2") (pinfunction "K_2") (pintype "unspecified"))
      (node (ref "LED6") (pin "2") (pinfunction "K_2") (pintype "unspecified"))
      (node (ref "Q_BMS") (pin "1") (pinfunction "S1_1") (pintype "unspecified"))
      (node (ref "R11") (pin "2") (pinfunction "2_2") (pintype "input"))
      (node (ref "R13") (pin "1") (pinfunction "1_1") (pintype "input"))
      (node (ref "R4") (pin "1") (pinfunction "1_1") (pintype "input"))
      (node (ref "R6") (pin "1") (pinfunction "1_1") (pintype "input"))
      (node (ref "R7") (pin "1") (pinfunction "1_1") (pintype "input"))
      (node (ref "R9") (pin "1") (pinfunction "1_1") (pintype "input"))
      (node (ref "U2") (pin "2") (pinfunction "VSS_2") (pintype "unspecified"))
      (node (ref "U3") (pin "4") (pinfunction "GND_4") (pintype "unspecified"))
      (node (ref "U4") (pin "1") (pinfunction "VSS_1") (pintype "unspecified"))
      (node (ref "U7") (pin "2") (pinfunction "GND_2") (pintype "unspecified"))
      (node (ref "U8") (pin "48") (pinfunction "VSSSMPS_48") (pintype "unspecified"))
      (node (ref "U8") (pin "49") (pinfunction "EP_49") (pintype "unspecified"))
      (node (ref "U_USB") (pin "1") (pinfunction "GND_1") (pintype "unspecified"))
    )
    (net (code "23") (name "Net-(FL1-RFO_in)") (class "Default")
      (node (ref "C15") (pin "2") (pinfunction "2_2") (pintype "input"))
      (node (ref "FL1") (pin "A1") (pinfunction "RFO_in_A1") (pintype "unspecified"))
      (node (ref "L3") (pin "1") (pinfunction "1_1") (pintype "unspecified"))
    )
    (net (code "24") (name "Net-(J_RF-SIG)") (class "Default")
      (node (ref "J_RF") (pin "1") (pinfunction "SIG_1") (pintype "unspecified"))
      (node (ref "U7") (pin "5") (pinfunction "INPUT_5") (pintype "unspecified"))
    )
    (net (code "25") (name "Net-(J_USB-CC1)") (class "Default")
      (node (ref "J_USB") (pin "A5") (pinfunction "CC1_A5") (pintype "unspecified"))
      (node (ref "R6") (pin "2") (pinfunction "2_2") (pintype "input"))
    )
    (net (code "26") (name "Net-(J_USB-CC2)") (class "Default")
      (node (ref "J_USB") (pin "B5") (pinfunction "CC2_B5") (pintype "unspecified"))
      (node (ref "R7") (pin "2") (pinfunction "2_2") (pintype "input"))
    )
    (net (code "27") (name "Net-(LED4-K)") (class "Default")
      (node (ref "LED4") (pin "2") (pinfunction "K_2") (pintype "unspecified"))
      (node (ref "R_STAT") (pin "1") (pinfunction "1_1") (pintype "unspecified"))
    )
    (net (code "28") (name "Net-(LED5-A)") (class "Default")
      (node (ref "LED5") (pin "1") (pinfunction "A_1") (pintype "unspecified"))
      (node (ref "R8") (pin "1") (pinfunction "1_1") (pintype "input"))
    )
    (net (code "29") (name "Net-(LED6-A)") (class "Default")
      (node (ref "LED6") (pin "1") (pinfunction "A_1") (pintype "unspecified"))
      (node (ref "R12") (pin "2") (pinfunction "2_2") (pintype "input"))
    )
    (net (code "30") (name "Net-(Q_BMS-G1)") (class "Default")
      (node (ref "Q_BMS") (pin "6") (pinfunction "G1_6") (pintype "unspecified"))
      (node (ref "U6") (pin "2") (pinfunction "COUT_2") (pintype "input"))
    )
    (net (code "31") (name "Net-(Q_BMS-G2)") (class "Default")
      (node (ref "Q_BMS") (pin "4") (pinfunction "G2_4") (pintype "unspecified"))
      (node (ref "U6") (pin "3") (pinfunction "DOUT_3") (pintype "input"))
    )
    (net (code "32") (name "Net-(Q_BMS-S2)") (class "Default")
      (node (ref "C40") (pin "1") (pinfunction "1_1") (pintype "unspecified"))
      (node (ref "C7") (pin "1") (pinfunction "1_1") (pintype "input"))
      (node (ref "J_BAT1") (pin "2") (pinfunction "2_2") (pintype "input"))
      (node (ref "J_BAT2") (pin "2") (pinfunction "2_2") (pintype "input"))
      (node (ref "J_BAT3") (pin "2") (pinfunction "2_2") (pintype "input"))
      (node (ref "J_BAT4") (pin "2") (pinfunction "2_2") (pintype "input"))
      (node (ref "Q_BMS") (pin "3") (pinfunction "S2_3") (pintype "unspecified"))
      (node (ref "U6") (pin "4") (pinfunction "VSS_4") (pintype "input"))
    )
    (net (code "33") (name "Net-(U2-PROG)") (class "Default")
      (node (ref "R9") (pin "2") (pinfunction "2_2") (pintype "input"))
      (node (ref "U2") (pin "5") (pinfunction "PROG_5") (pintype "unspecified"))
    )
    (net (code "34") (name "Net-(U2-STAT)") (class "Default")
      (node (ref "R_STAT") (pin "2") (pinfunction "2_2") (pintype "unspecified"))
      (node (ref "U2") (pin "1") (pinfunction "STAT_1") (pintype "unspecified"))
    )
    (net (code "35") (name "Net-(U2-VBAT)") (class "Default")
      (node (ref "C38") (pin "2") (pinfunction "2_2") (pintype "input"))
      (node (ref "C7") (pin "2") (pinfunction "2_2") (pintype "input"))
      (node (ref "J_BAT1") (pin "1") (pinfunction "1_1") (pintype "input"))
      (node (ref "J_BAT2") (pin "1") (pinfunction "1_1") (pintype "input"))
      (node (ref "J_BAT3") (pin "1") (pinfunction "1_1") (pintype "input"))
      (node (ref "J_BAT4") (pin "1") (pinfunction "1_1") (pintype "input"))
      (node (ref "J_PWRSWITCH") (pin "2") (pinfunction "2_2") (pintype "input"))
      (node (ref "R10") (pin "2") (pinfunction "2_2") (pintype "input"))
      (node (ref "U2") (pin "3") (pinfunction "VBAT_3") (pintype "unspecified"))
    )
    (net (code "36") (name "Net-(U3-EN)") (class "Default")
      (node (ref "R14") (pin "2") (pinfunction "2_2") (pintype "input"))
      (node (ref "R15") (pin "2") (pinfunction "2_2") (pintype "input"))
      (node (ref "U3") (pin "2") (pinfunction "EN_2") (pintype "unspecified"))
    )
    (net (code "37") (name "Net-(U3-FB)") (class "Default")
      (node (ref "R13") (pin "2") (pinfunction "2_2") (pintype "input"))
      (node (ref "R_FB1") (pin "2") (pinfunction "2_2") (pintype "input"))
      (node (ref "U3") (pin "1") (pinfunction "FB_1") (pintype "unspecified"))
    )
    (net (code "38") (name "Net-(U3-SW)") (class "Default")
      (node (ref "L1") (pin "1") (pinfunction "1_1") (pintype "unspecified"))
      (node (ref "U3") (pin "5") (pinfunction "SW_5") (pintype "unspecified"))
    )
    (net (code "39") (name "Net-(U6-BAT)") (class "Default")
      (node (ref "C40") (pin "2") (pinfunction "2_2") (pintype "unspecified"))
      (node (ref "R10") (pin "1") (pinfunction "1_1") (pintype "input"))
      (node (ref "U6") (pin "5") (pinfunction "BAT_5") (pintype "input"))
    )
    (net (code "40") (name "Net-(U6-V-)") (class "Default")
      (node (ref "R11") (pin "1") (pinfunction "1_1") (pintype "input"))
      (node (ref "U6") (pin "6") (pinfunction "V-_6") (pintype "input"))
    )
    (net (code "41") (name "Net-(U8-NRST)") (class "Default")
      (node (ref "R5") (pin "2") (pinfunction "2_2") (pintype "input"))
      (node (ref "U8") (pin "18") (pinfunction "NRST_18") (pintype "unspecified"))
    )
    (net (code "42") (name "Net-(U8-VLXSMPS)") (class "Default")
      (node (ref "L_SMPS") (pin "1") (pinfunction "1_1") (pintype "unspecified"))
      (node (ref "U8") (pin "47") (pinfunction "VLXSMPS_47") (pintype "unspecified"))
    )
    (net (code "43") (name "Net-(U_USB-V3)") (class "Default")
      (node (ref "C29") (pin "2") (pinfunction "2_2") (pintype "unspecified"))
      (node (ref "U_USB") (pin "4") (pinfunction "V3_4") (pintype "unspecified"))
    )
    (net (code "44") (name "VBAT") (class "Default")
      (node (ref "C27") (pin "2") (pinfunction "2_2") (pintype "unspecified"))
      (node (ref "C43") (pin "2") (pinfunction "2_2") (pintype "unspecified"))
      (node (ref "C44") (pin "2") (pinfunction "2_2") (pintype "input"))
      (node (ref "J_PWRSWITCH") (pin "1") (pinfunction "1_1") (pintype "input"))
      (node (ref "L1") (pin "2") (pinfunction "2_2") (pintype "unspecified"))
      (node (ref "R15") (pin "1") (pinfunction "1_1") (pintype "input"))
      (node (ref "R8") (pin "2") (pinfunction "2_2") (pintype "input"))
      (node (ref "U3") (pin "3") (pinfunction "VIN_3") (pintype "unspecified"))
      (node (ref "U4") (pin "3") (pinfunction "VIN_3") (pintype "unspecified"))
    )
    (net (code "45") (name "VBUS_5V") (class "Default")
      (node (ref "C39") (pin "1") (pinfunction "1_1") (pintype "input"))
      (node (ref "J_USB") (pin "A4B9") (pinfunction "VBUS_A4B9") (pintype "unspecified"))
      (node (ref "J_USB") (pin "B4A9") (pinfunction "VBUS_B4A9") (pintype "unspecified"))
      (node (ref "LED4") (pin "1") (pinfunction "A_1") (pintype "unspecified"))
      (node (ref "U2") (pin "4") (pinfunction "VDD_4") (pintype "unspecified"))
    )
    (net (code "46") (name "unconnected-(J_USB-SBU1-PadA8)") (class "Default")
      (node (ref "J_USB") (pin "A8") (pinfunction "SBU1_A8") (pintype "unspecified"))
    )
    (net (code "47") (name "unconnected-(J_USB-SBU2-PadB8)") (class "Default")
      (node (ref "J_USB") (pin "B8") (pinfunction "SBU2_B8") (pintype "unspecified"))
    )
    (net (code "48") (name "unconnected-(Q_BMS-D1{slash}D2-Pad2)") (class "Default")
      (node (ref "Q_BMS") (pin "2") (pinfunction "D1/D2_2") (pintype "unspecified"))
    )
    (net (code "49") (name "unconnected-(Q_BMS-D1{slash}D2-Pad5)") (class "Default")
      (node (ref "Q_BMS") (pin "5") (pinfunction "D1/D2_5") (pintype "unspecified"))
    )
    (net (code "50") (name "unconnected-(SW1-Pad3)") (class "Default")
      (node (ref "SW1") (pin "3") (pinfunction "3_3") (pintype "unspecified"))
    )
    (net (code "51") (name "unconnected-(SW1-Pad4)") (class "Default")
      (node (ref "SW1") (pin "4") (pinfunction "4_4") (pintype "unspecified"))
    )
    (net (code "52") (name "unconnected-(U6-NC-Pad1)") (class "Default")
      (node (ref "U6") (pin "1") (pinfunction "NC_1") (pintype "input"))
    )
    (net (code "53") (name "unconnected-(U8-OSC_IN-Pad26)") (class "Default")
      (node (ref "U8") (pin "26") (pinfunction "OSC_IN_26") (pintype "unspecified"))
    )
    (net (code "54") (name "unconnected-(U8-OSC_OUT-Pad27)") (class "Default")
      (node (ref "U8") (pin "27") (pinfunction "OSC_OUT_27") (pintype "unspecified"))
    )
    (net (code "55") (name "unconnected-(U8-PA1-Pad8)") (class "Default")
      (node (ref "U8") (pin "8") (pinfunction "PA1_8") (pintype "unspecified"))
    )
    (net (code "56") (name "unconnected-(U8-PA4-Pad12)") (class "Default")
      (node (ref "U8") (pin "12") (pinfunction "PA4_12") (pintype "unspecified"))
    )
    (net (code "57") (name "unconnected-(U8-PA5-Pad13)") (class "Default")
      (node (ref "U8") (pin "13") (pinfunction "PA5_13") (pintype "unspecified"))
    )
    (net (code "58") (name "unconnected-(U8-PA6-Pad14)") (class "Default")
      (node (ref "U8") (pin "14") (pinfunction "PA6_14") (pintype "unspecified"))
    )
    (net (code "59") (name "unconnected-(U8-PA11-Pad34)") (class "Default")
      (node (ref "U8") (pin "34") (pinfunction "PA11_34") (pintype "unspecified"))
    )
    (net (code "60") (name "unconnected-(U8-PA12-Pad35)") (class "Default")
      (node (ref "U8") (pin "35") (pinfunction "PA12_35") (pintype "unspecified"))
    )
    (net (code "61") (name "unconnected-(U8-PA15-Pad43)") (class "Default")
      (node (ref "U8") (pin "43") (pinfunction "PA15_43") (pintype "unspecified"))
    )
    (net (code "62") (name "unconnected-(U8-PB0-VDD_TCXO-Pad30)") (class "Default")
      (node (ref "U8") (pin "30") (pinfunction "PB0-VDD_TCXO_30") (pintype "unspecified"))
    )
    (net (code "63") (name "unconnected-(U8-PB2-Pad31)") (class "Default")
      (node (ref "U8") (pin "31") (pinfunction "PB2_31") (pintype "unspecified"))
    )
    (net (code "64") (name "unconnected-(U8-PB3-Pad1)") (class "Default")
      (node (ref "U8") (pin "1") (pinfunction "PB3_1") (pintype "unspecified"))
    )
    (net (code "65") (name "unconnected-(U8-PB4-Pad2)") (class "Default")
      (node (ref "U8") (pin "2") (pinfunction "PB4_2") (pintype "unspecified"))
    )
    (net (code "66") (name "unconnected-(U8-PB5-Pad3)") (class "Default")
      (node (ref "U8") (pin "3") (pinfunction "PB5_3") (pintype "unspecified"))
    )
    (net (code "67") (name "unconnected-(U8-PB6-Pad4)") (class "Default")
      (node (ref "U8") (pin "4") (pinfunction "PB6_4") (pintype "unspecified"))
    )
    (net (code "68") (name "unconnected-(U8-PB7-Pad5)") (class "Default")
      (node (ref "U8") (pin "5") (pinfunction "PB7_5") (pintype "unspecified"))
    )
    (net (code "69") (name "unconnected-(U8-PB8-Pad6)") (class "Default")
      (node (ref "U8") (pin "6") (pinfunction "PB8_6") (pintype "unspecified"))
    )
    (net (code "70") (name "unconnected-(U8-PB12-Pad32)") (class "Default")
      (node (ref "U8") (pin "32") (pinfunction "PB12_32") (pintype "unspecified"))
    )
    (net (code "71") (name "unconnected-(U8-PC13-Pad38)") (class "Default")
      (node (ref "U8") (pin "38") (pinfunction "PC13_38") (pintype "unspecified"))
    )
    (net (code "72") (name "unconnected-(U8-PC14-OSC32_IN-Pad39)") (class "Default")
      (node (ref "U8") (pin "39") (pinfunction "PC14-OSC32_IN_39") (pintype "unspecified"))
    )
    (net (code "73") (name "unconnected-(U8-PC15-OSC32_OUT-Pad40)") (class "Default")
      (node (ref "U8") (pin "40") (pinfunction "PC15-OSC32_OUT_40") (pintype "unspecified"))
    )
    (net (code "74") (name "unconnected-(U8-RFO_HP-Pad23)") (class "Default")
      (node (ref "U8") (pin "23") (pinfunction "RFO_HP_23") (pintype "unspecified"))
    )
    (net (code "75") (name "unconnected-(U_USB-CTS#-Pad9)") (class "Default")
      (node (ref "U_USB") (pin "9") (pinfunction "CTS#_9") (pintype "unspecified"))
    )
    (net (code "76") (name "unconnected-(U_USB-DCD#-Pad12)") (class "Default")
      (node (ref "U_USB") (pin "12") (pinfunction "DCD#_12") (pintype "unspecified"))
    )
    (net (code "77") (name "unconnected-(U_USB-DSR#-Pad10)") (class "Default")
      (node (ref "U_USB") (pin "10") (pinfunction "DSR#_10") (pintype "unspecified"))
    )
    (net (code "78") (name "unconnected-(U_USB-DTR#-Pad13)") (class "Default")
      (node (ref "U_USB") (pin "13") (pinfunction "DTR#_13") (pintype "unspecified"))
    )
    (net (code "79") (name "unconnected-(U_USB-NC.-Pad7)") (class "Default")
      (node (ref "U_USB") (pin "7") (pinfunction "NC._7") (pintype "unspecified"))
    )
    (net (code "80") (name "unconnected-(U_USB-OUT#-Pad8)") (class "Default")
      (node (ref "U_USB") (pin "8") (pinfunction "OUT#_8") (pintype "unspecified"))
    )
    (net (code "81") (name "unconnected-(U_USB-R232-Pad15)") (class "Default")
      (node (ref "U_USB") (pin "15") (pinfunction "R232_15") (pintype "unspecified"))
    )
    (net (code "82") (name "unconnected-(U_USB-RI#-Pad11)") (class "Default")
      (node (ref "U_USB") (pin "11") (pinfunction "RI#_11") (pintype "unspecified"))
    )
    (net (code "83") (name "unconnected-(U_USB-RTS#-Pad14)") (class "Default")
      (node (ref "U_USB") (pin "14") (pinfunction "RTS#_14") (pintype "unspecified"))
    )
  )
)
